# salidas_programables_easy_eda.net
KiCad netlist of a schematic drawn in EasyEDA
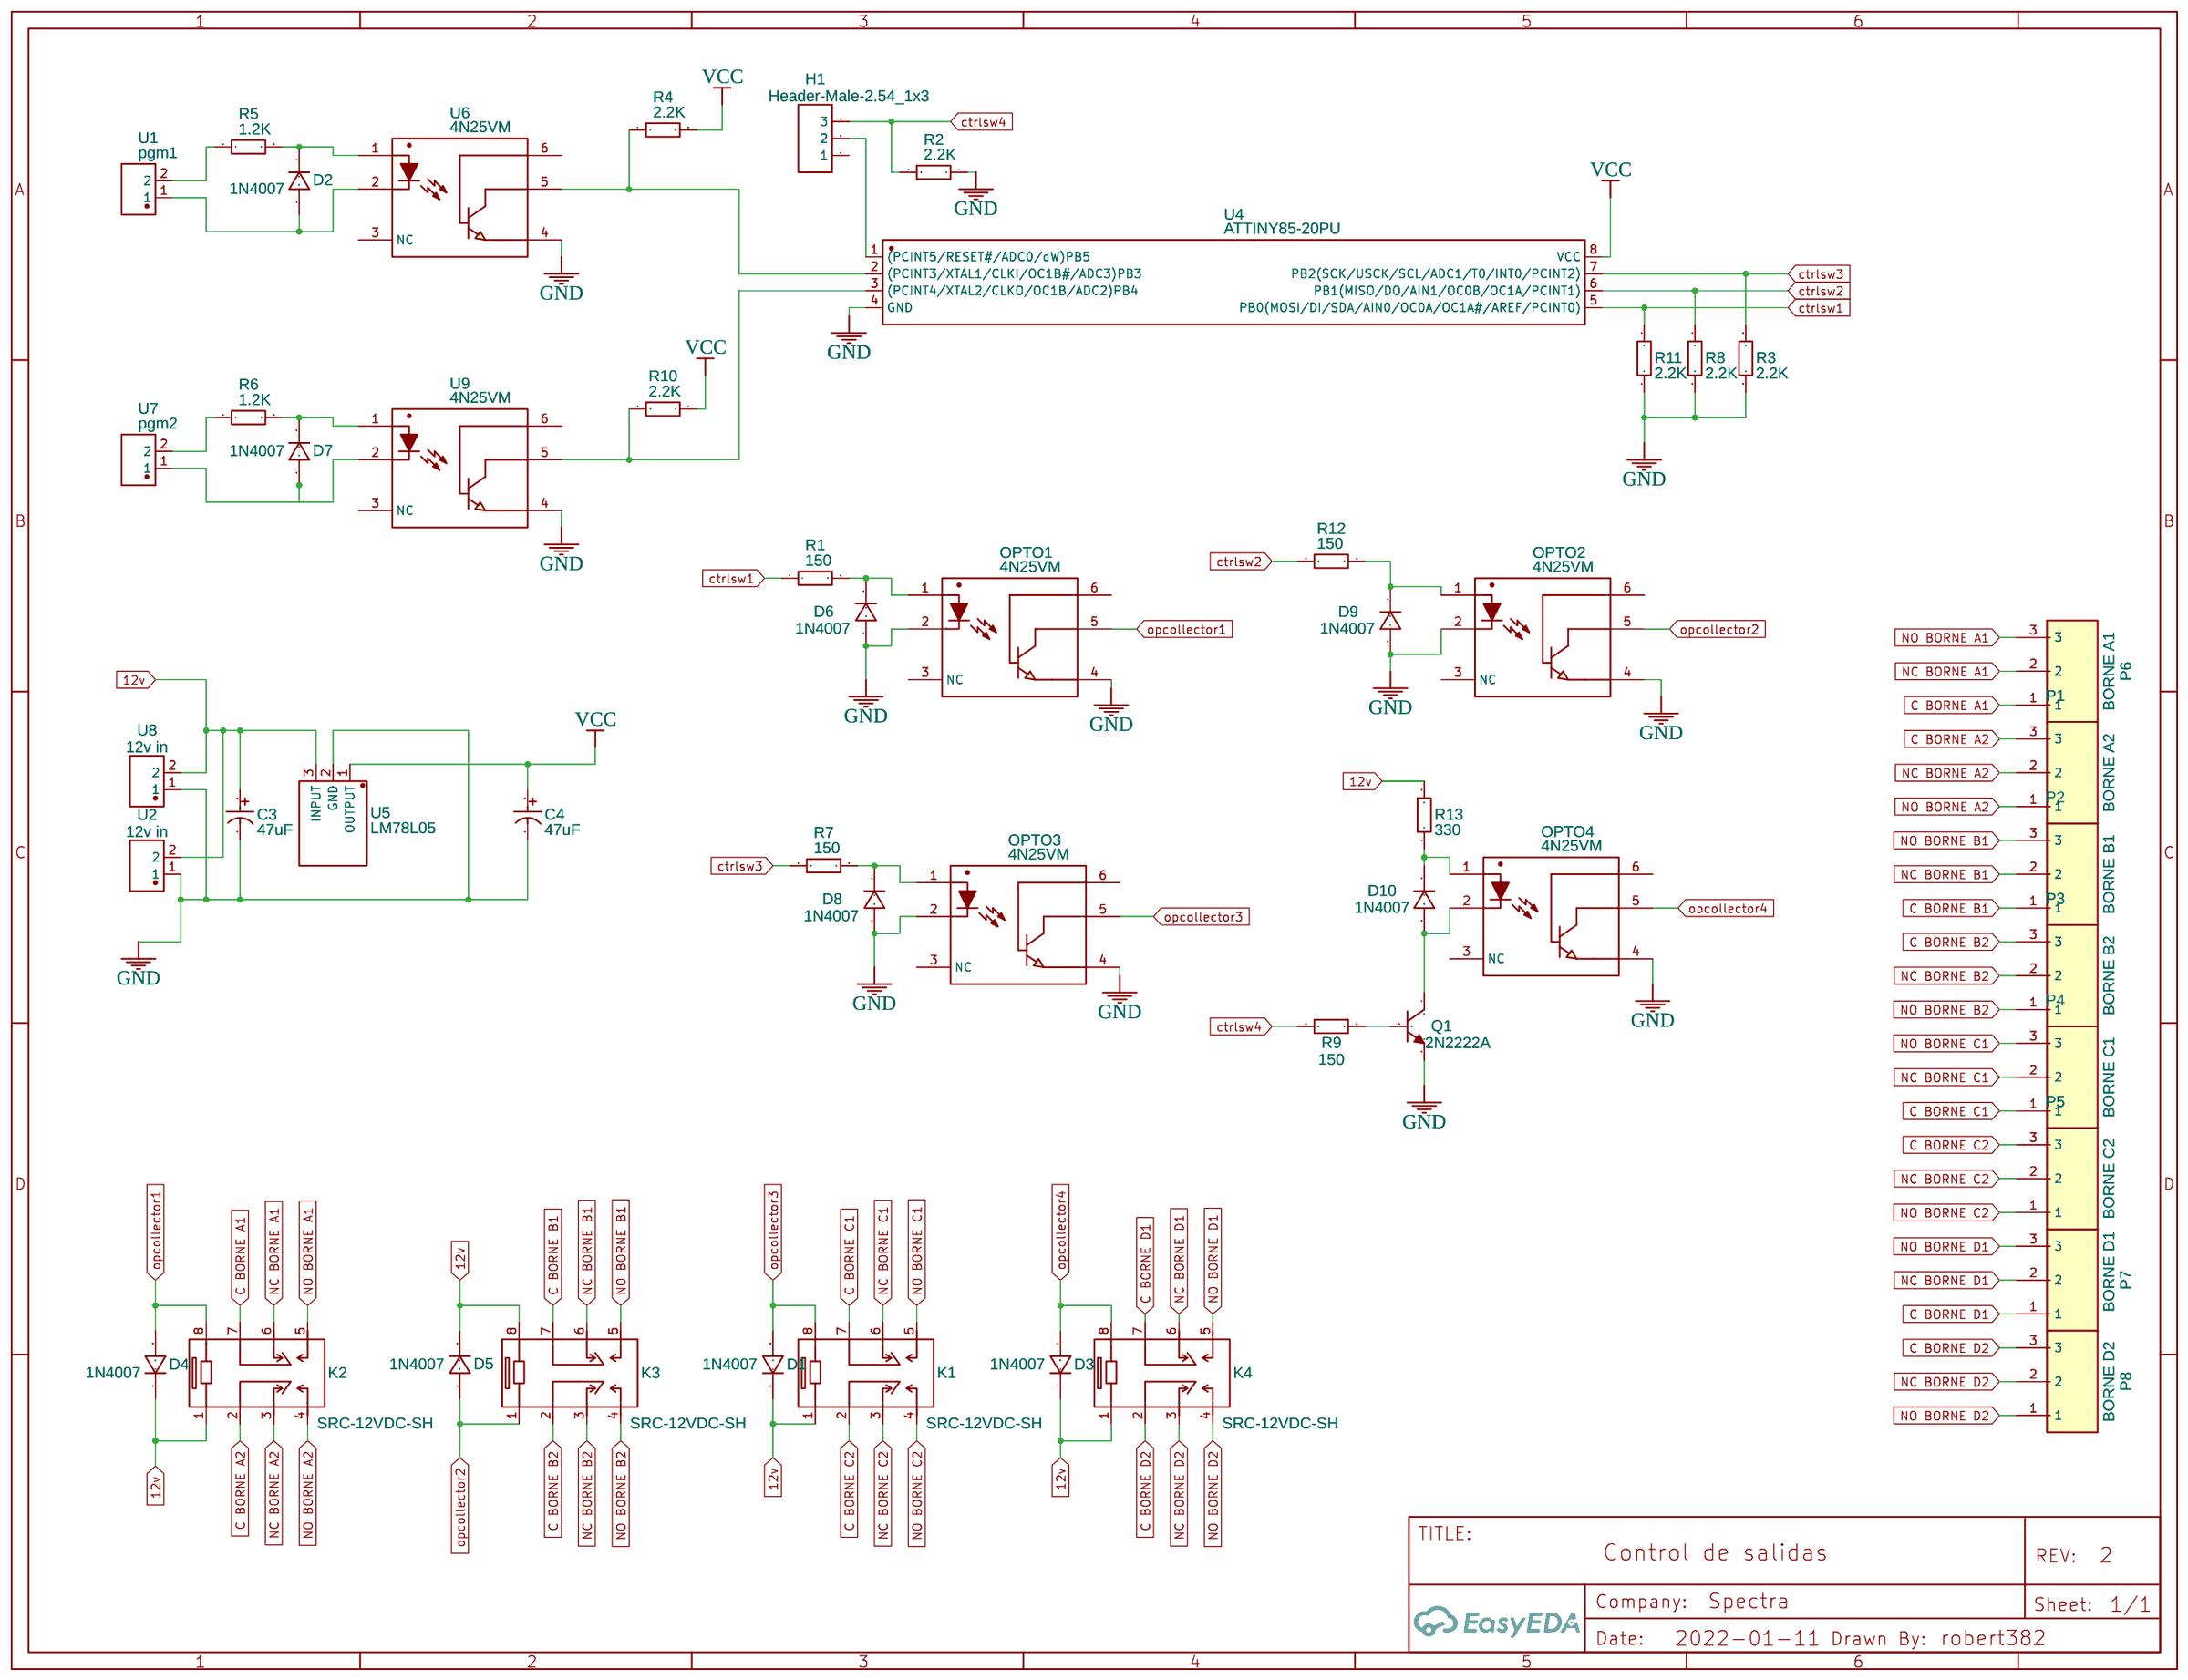
[diagram p0: schematic sheet]

(export (version "E")
  (design (tool "Eeschema 10.0.6"))
  (components
    (comp (ref "C3")
      (value "47uF")
      (fields
        (field (name "BOM_Manufacturer Part") "SH476M035F0800")
        (field (name "BOM_Supplier Part") "C99831")
      )
      (libsource (lib "") (part "SH476M035F0800"))
    )
    (comp (ref "C4")
      (value "47uF")
      (fields
        (field (name "BOM_Manufacturer Part") "SH476M035F0800")
        (field (name "BOM_Supplier Part") "C99831")
      )
      (libsource (lib "") (part "SH476M035F0800"))
    )
    (comp (ref "D1")
      (value "1N4007")
      (fields (field (name "BOM_Supplier Part") "C169152"))
      (libsource (lib "") (part "1N4007-C169152_1"))
    )
    (comp (ref "D2")
      (value "1N4007")
      (fields (field (name "BOM_Supplier Part") "C169152"))
      (libsource (lib "") (part "1N4007-C169152"))
    )
    (comp (ref "D3")
      (value "1N4007")
      (fields (field (name "BOM_Supplier Part") "C169152"))
      (libsource (lib "") (part "1N4007-C169152_1"))
    )
    (comp (ref "D4")
      (value "1N4007")
      (fields (field (name "BOM_Supplier Part") "C169152"))
      (libsource (lib "") (part "1N4007-C169152_1"))
    )
    (comp (ref "D5")
      (value "1N4007")
      (fields (field (name "BOM_Supplier Part") "C169152"))
      (libsource (lib "") (part "1N4007-C169152"))
    )
    (comp (ref "D6")
      (value "1N4007")
      (fields (field (name "BOM_Supplier Part") "C169152"))
      (libsource (lib "") (part "1N4007-C169152"))
    )
    (comp (ref "D7")
      (value "1N4007")
      (fields (field (name "BOM_Supplier Part") "C169152"))
      (libsource (lib "") (part "1N4007-C169152"))
    )
    (comp (ref "D8")
      (value "1N4007")
      (fields (field (name "BOM_Supplier Part") "C169152"))
      (libsource (lib "") (part "1N4007-C169152"))
    )
    (comp (ref "D9")
      (value "1N4007")
      (fields (field (name "BOM_Supplier Part") "C169152"))
      (libsource (lib "") (part "1N4007-C169152"))
    )
    (comp (ref "D10")
      (value "1N4007")
      (fields (field (name "BOM_Supplier Part") "C169152"))
      (libsource (lib "") (part "1N4007-C169152"))
    )
    (comp (ref "H1")
      (value "Header-Male-2.54_1x3")
      (fields
        (field (name "BOM_Manufacturer Part") "Header2.54mm 1*3P")
        (field (name "BOM_Supplier Part") "C49257")
      )
      (libsource (lib "") (part "Header-Male-2.54_1x3"))
    )
    (comp (ref "K1")
      (value "SRC-12VDC-SH")
      (fields (field (name "BOM_Supplier Part") "C192464"))
      (libsource (lib "") (part "SRC-12VDC-SH"))
    )
    (comp (ref "K2")
      (value "SRC-12VDC-SH")
      (fields (field (name "BOM_Supplier Part") "C192464"))
      (libsource (lib "") (part "SRC-12VDC-SH"))
    )
    (comp (ref "K3")
      (value "SRC-12VDC-SH")
      (fields (field (name "BOM_Supplier Part") "C192464"))
      (libsource (lib "") (part "SRC-12VDC-SH"))
    )
    (comp (ref "K4")
      (value "SRC-12VDC-SH")
      (fields (field (name "BOM_Supplier Part") "C192464"))
      (libsource (lib "") (part "SRC-12VDC-SH"))
    )
    (comp (ref "OPTO1")
      (value "4N25VM")
      (fields (field (name "BOM_Supplier Part") "C898943"))
      (libsource (lib "") (part "4N25VM"))
    )
    (comp (ref "OPTO2")
      (value "4N25VM")
      (fields (field (name "BOM_Supplier Part") "C898943"))
      (libsource (lib "") (part "4N25VM"))
    )
    (comp (ref "OPTO3")
      (value "4N25VM")
      (fields (field (name "BOM_Supplier Part") "C898943"))
      (libsource (lib "") (part "4N25VM"))
    )
    (comp (ref "OPTO4")
      (value "4N25VM")
      (fields (field (name "BOM_Supplier Part") "C898943"))
      (libsource (lib "") (part "4N25VM"))
    )
    (comp (ref "P1")
      (value "BORNE A2")
      (fields
        (field (name "BOM_Manufacturer Part") "WJ126V-5.0-3P")
        (field (name "BOM_Supplier Part") "C8401")
      )
      (libsource (lib "") (part "WJ126V-5.0-3P"))
    )
    (comp (ref "P2")
      (value "BORNE B1")
      (fields
        (field (name "BOM_Manufacturer Part") "WJ126V-5.0-3P")
        (field (name "BOM_Supplier Part") "C8401")
      )
      (libsource (lib "") (part "WJ126V-5.0-3P"))
    )
    (comp (ref "P3")
      (value "BORNE B2")
      (fields
        (field (name "BOM_Manufacturer Part") "WJ126V-5.0-3P")
        (field (name "BOM_Supplier Part") "C8401")
      )
      (libsource (lib "") (part "WJ126V-5.0-3P"))
    )
    (comp (ref "P4")
      (value "BORNE C1")
      (fields
        (field (name "BOM_Manufacturer Part") "WJ126V-5.0-3P")
        (field (name "BOM_Supplier Part") "C8401")
      )
      (libsource (lib "") (part "WJ126V-5.0-3P"))
    )
    (comp (ref "P5")
      (value "BORNE C2")
      (fields
        (field (name "BOM_Manufacturer Part") "WJ126V-5.0-3P")
        (field (name "BOM_Supplier Part") "C8401")
      )
      (libsource (lib "") (part "WJ126V-5.0-3P"))
    )
    (comp (ref "P6")
      (value "BORNE A1")
      (fields
        (field (name "BOM_Manufacturer Part") "WJ126V-5.0-3P")
        (field (name "BOM_Supplier Part") "C8401")
      )
      (libsource (lib "") (part "WJ126V-5.0-3P"))
    )
    (comp (ref "P7")
      (value "BORNE D1")
      (fields
        (field (name "BOM_Manufacturer Part") "WJ126V-5.0-3P")
        (field (name "BOM_Supplier Part") "C8401")
      )
      (libsource (lib "") (part "WJ126V-5.0-3P"))
    )
    (comp (ref "P8")
      (value "BORNE D2")
      (fields
        (field (name "BOM_Manufacturer Part") "WJ126V-5.0-3P")
        (field (name "BOM_Supplier Part") "C8401")
      )
      (libsource (lib "") (part "WJ126V-5.0-3P"))
    )
    (comp (ref "Q1")
      (value "2N2222A")
      (fields (field (name "BOM_Supplier Part") "C358533"))
      (libsource (lib "") (part "2N2222A"))
    )
    (comp (ref "R1")
      (value "150")
      (fields (field (name "BOM_Supplier Part") "C119160"))
      (libsource (lib "") (part "MF1/8W-150Ω±1% T52"))
    )
    (comp (ref "R2")
      (value "2.2K")
      (fields (field (name "BOM_Supplier Part") "C119331"))
      (libsource (lib "") (part "MF1/4W-2.2KΩ±1% T52_1"))
    )
    (comp (ref "R3")
      (value "2.2K")
      (fields (field (name "BOM_Supplier Part") "C119331"))
      (libsource (lib "") (part "MF1/4W-2.2KΩ±1% T52_2"))
    )
    (comp (ref "R4")
      (value "2.2K")
      (fields (field (name "BOM_Supplier Part") "C119331"))
      (libsource (lib "") (part "MF1/4W-2.2KΩ±1% T52"))
    )
    (comp (ref "R5")
      (value "1.2K")
      (fields (field (name "BOM_Supplier Part") "C119872"))
      (libsource (lib "") (part "CF1/6W-1.2KΩ±5% T52"))
    )
    (comp (ref "R6")
      (value "1.2K")
      (fields (field (name "BOM_Supplier Part") "C119872"))
      (libsource (lib "") (part "CF1/6W-1.2KΩ±5% T52"))
    )
    (comp (ref "R7")
      (value "150")
      (fields (field (name "BOM_Supplier Part") "C119160"))
      (libsource (lib "") (part "MF1/8W-150Ω±1% T52"))
    )
    (comp (ref "R8")
      (value "2.2K")
      (fields (field (name "BOM_Supplier Part") "C119331"))
      (libsource (lib "") (part "MF1/4W-2.2KΩ±1% T52_2"))
    )
    (comp (ref "R9")
      (value "150")
      (fields (field (name "BOM_Supplier Part") "C119160"))
      (libsource (lib "") (part "MF1/8W-150Ω±1% T52"))
    )
    (comp (ref "R10")
      (value "2.2K")
      (fields (field (name "BOM_Supplier Part") "C119331"))
      (libsource (lib "") (part "MF1/4W-2.2KΩ±1% T52_1"))
    )
    (comp (ref "R11")
      (value "2.2K")
      (fields (field (name "BOM_Supplier Part") "C119331"))
      (libsource (lib "") (part "MF1/4W-2.2KΩ±1% T52_2"))
    )
    (comp (ref "R12")
      (value "150")
      (fields (field (name "BOM_Supplier Part") "C119160"))
      (libsource (lib "") (part "MF1/8W-150Ω±1% T52"))
    )
    (comp (ref "R13")
      (value "330")
      (fields (field (name "BOM_Supplier Part") "C10322"))
      (libsource (lib "") (part "330Ω (331) ±5%"))
    )
    (comp (ref "U1")
      (value "pgm1")
      (fields
        (field (name "BOM_Manufacturer Part") "KY0200500000G")
        (field (name "BOM_Supplier Part") "C967069")
      )
      (libsource (lib "") (part "KY0200500000G"))
    )
    (comp (ref "U2")
      (value "12v in")
      (fields
        (field (name "BOM_Manufacturer Part") "KY0200500000G")
        (field (name "BOM_Supplier Part") "C967069")
      )
      (libsource (lib "") (part "KY0200500000G"))
    )
    (comp (ref "U4")
      (value "ATTINY85-20PU")
      (fields (field (name "BOM_Supplier Part") "C965497"))
      (libsource (lib "") (part "ATTINY85-20PU"))
    )
    (comp (ref "U5")
      (value "LM78L05")
      (fields
        (field (name "BOM_Manufacturer Part") "LM78L05ACZXA")
        (field (name "BOM_Supplier Part") "C236945")
      )
      (libsource (lib "") (part "LM78L05ACZXA"))
    )
    (comp (ref "U6")
      (value "4N25VM")
      (fields (field (name "BOM_Supplier Part") "C898943"))
      (libsource (lib "") (part "4N25VM_1"))
    )
    (comp (ref "U7")
      (value "pgm2")
      (fields
        (field (name "BOM_Manufacturer Part") "KY0200500000G")
        (field (name "BOM_Supplier Part") "C967069")
      )
      (libsource (lib "") (part "KY0200500000G"))
    )
    (comp (ref "U8")
      (value "12v in")
      (fields
        (field (name "BOM_Manufacturer Part") "KY0200500000G")
        (field (name "BOM_Supplier Part") "C967069")
      )
      (libsource (lib "") (part "KY0200500000G"))
    )
    (comp (ref "U9")
      (value "4N25VM")
      (fields (field (name "BOM_Supplier Part") "C898943"))
      (libsource (lib "") (part "4N25VM_1"))
    )
  )
  (nets
    (net (code "1") (name "12v") (class "Default")
      (node (ref "C3") (pin "1") (pinfunction "1_1") (pintype "input"))
      (node (ref "D1") (pin "1") (pinfunction "1_1") (pintype "unspecified"))
      (node (ref "D3") (pin "1") (pinfunction "1_1") (pintype "unspecified"))
      (node (ref "D4") (pin "1") (pinfunction "1_1") (pintype "unspecified"))
      (node (ref "D5") (pin "1") (pinfunction "1_1") (pintype "unspecified"))
      (node (ref "K1") (pin "1") (pinfunction "1_1") (pintype "unspecified"))
      (node (ref "K2") (pin "1") (pinfunction "1_1") (pintype "unspecified"))
      (node (ref "K3") (pin "8") (pinfunction "8_8") (pintype "unspecified"))
      (node (ref "K4") (pin "1") (pinfunction "1_1") (pintype "unspecified"))
      (node (ref "R13") (pin "2") (pinfunction "2_2") (pintype "unspecified"))
      (node (ref "U2") (pin "2") (pinfunction "2_2") (pintype "unspecified"))
      (node (ref "U5") (pin "3") (pinfunction "INPUT_3") (pintype "unspecified"))
      (node (ref "U8") (pin "2") (pinfunction "2_2") (pintype "unspecified"))
    )
    (net (code "2") (name "C BORNE A1") (class "Default")
      (node (ref "K2") (pin "7") (pinfunction "7_7") (pintype "unspecified"))
      (node (ref "P6") (pin "1") (pinfunction "1_1") (pintype "input"))
    )
    (net (code "3") (name "C BORNE A2") (class "Default")
      (node (ref "K2") (pin "2") (pinfunction "2_2") (pintype "unspecified"))
      (node (ref "P1") (pin "3") (pinfunction "3_3") (pintype "input"))
    )
    (net (code "4") (name "C BORNE B1") (class "Default")
      (node (ref "K3") (pin "7") (pinfunction "7_7") (pintype "unspecified"))
      (node (ref "P2") (pin "1") (pinfunction "1_1") (pintype "input"))
    )
    (net (code "5") (name "C BORNE B2") (class "Default")
      (node (ref "K3") (pin "2") (pinfunction "2_2") (pintype "unspecified"))
      (node (ref "P3") (pin "3") (pinfunction "3_3") (pintype "input"))
    )
    (net (code "6") (name "C BORNE C1") (class "Default")
      (node (ref "K1") (pin "7") (pinfunction "7_7") (pintype "unspecified"))
      (node (ref "P4") (pin "1") (pinfunction "1_1") (pintype "input"))
    )
    (net (code "7") (name "C BORNE C2") (class "Default")
      (node (ref "K1") (pin "2") (pinfunction "2_2") (pintype "unspecified"))
      (node (ref "P5") (pin "3") (pinfunction "3_3") (pintype "input"))
    )
    (net (code "8") (name "C BORNE D1") (class "Default")
      (node (ref "K4") (pin "7") (pinfunction "7_7") (pintype "unspecified"))
      (node (ref "P7") (pin "1") (pinfunction "1_1") (pintype "input"))
    )
    (net (code "9") (name "C BORNE D2") (class "Default")
      (node (ref "K4") (pin "2") (pinfunction "2_2") (pintype "unspecified"))
      (node (ref "P8") (pin "3") (pinfunction "3_3") (pintype "input"))
    )
    (net (code "10") (name "GND") (class "Default")
      (node (ref "C3") (pin "2") (pinfunction "2_2") (pintype "input"))
      (node (ref "C4") (pin "2") (pinfunction "2_2") (pintype "input"))
      (node (ref "D6") (pin "2") (pinfunction "2_2") (pintype "unspecified"))
      (node (ref "D8") (pin "2") (pinfunction "2_2") (pintype "unspecified"))
      (node (ref "D9") (pin "2") (pinfunction "2_2") (pintype "unspecified"))
      (node (ref "OPTO1") (pin "2") (pinfunction "C_2") (pintype "unspecified"))
      (node (ref "OPTO1") (pin "4") (pinfunction "E_4") (pintype "unspecified"))
      (node (ref "OPTO2") (pin "2") (pinfunction "C_2") (pintype "unspecified"))
      (node (ref "OPTO2") (pin "4") (pinfunction "E_4") (pintype "unspecified"))
      (node (ref "OPTO3") (pin "2") (pinfunction "C_2") (pintype "unspecified"))
      (node (ref "OPTO3") (pin "4") (pinfunction "E_4") (pintype "unspecified"))
      (node (ref "OPTO4") (pin "4") (pinfunction "E_4") (pintype "unspecified"))
      (node (ref "Q1") (pin "3") (pinfunction "E_3") (pintype "unspecified"))
      (node (ref "R11") (pin "1") (pinfunction "1_1") (pintype "unspecified"))
      (node (ref "R2") (pin "1") (pinfunction "1_1") (pintype "unspecified"))
      (node (ref "R3") (pin "1") (pinfunction "1_1") (pintype "unspecified"))
      (node (ref "R8") (pin "1") (pinfunction "1_1") (pintype "unspecified"))
      (node (ref "U2") (pin "1") (pinfunction "1_1") (pintype "unspecified"))
      (node (ref "U4") (pin "4") (pinfunction "GND_4") (pintype "unspecified"))
      (node (ref "U5") (pin "2") (pinfunction "GND_2") (pintype "unspecified"))
      (node (ref "U6") (pin "4") (pinfunction "E_4") (pintype "unspecified"))
      (node (ref "U8") (pin "1") (pinfunction "1_1") (pintype "unspecified"))
      (node (ref "U9") (pin "4") (pinfunction "E_4") (pintype "unspecified"))
    )
    (net (code "11") (name "NC BORNE A1") (class "Default")
      (node (ref "K2") (pin "6") (pinfunction "6_6") (pintype "unspecified"))
      (node (ref "P6") (pin "2") (pinfunction "2_2") (pintype "input"))
    )
    (net (code "12") (name "NC BORNE A2") (class "Default")
      (node (ref "K2") (pin "3") (pinfunction "3_3") (pintype "unspecified"))
      (node (ref "P1") (pin "2") (pinfunction "2_2") (pintype "input"))
    )
    (net (code "13") (name "NC BORNE B1") (class "Default")
      (node (ref "K3") (pin "6") (pinfunction "6_6") (pintype "unspecified"))
      (node (ref "P2") (pin "2") (pinfunction "2_2") (pintype "input"))
    )
    (net (code "14") (name "NC BORNE B2") (class "Default")
      (node (ref "K3") (pin "3") (pinfunction "3_3") (pintype "unspecified"))
      (node (ref "P3") (pin "2") (pinfunction "2_2") (pintype "input"))
    )
    (net (code "15") (name "NC BORNE C1") (class "Default")
      (node (ref "K1") (pin "6") (pinfunction "6_6") (pintype "unspecified"))
      (node (ref "P4") (pin "2") (pinfunction "2_2") (pintype "input"))
    )
    (net (code "16") (name "NC BORNE C2") (class "Default")
      (node (ref "K1") (pin "3") (pinfunction "3_3") (pintype "unspecified"))
      (node (ref "P5") (pin "2") (pinfunction "2_2") (pintype "input"))
    )
    (net (code "17") (name "NC BORNE D1") (class "Default")
      (node (ref "K4") (pin "6") (pinfunction "6_6") (pintype "unspecified"))
      (node (ref "P7") (pin "2") (pinfunction "2_2") (pintype "input"))
    )
    (net (code "18") (name "NC BORNE D2") (class "Default")
      (node (ref "K4") (pin "3") (pinfunction "3_3") (pintype "unspecified"))
      (node (ref "P8") (pin "2") (pinfunction "2_2") (pintype "input"))
    )
    (net (code "19") (name "NO BORNE A1") (class "Default")
      (node (ref "K2") (pin "5") (pinfunction "5_5") (pintype "unspecified"))
      (node (ref "P6") (pin "3") (pinfunction "3_3") (pintype "input"))
    )
    (net (code "20") (name "NO BORNE A2") (class "Default")
      (node (ref "K2") (pin "4") (pinfunction "4_4") (pintype "unspecified"))
      (node (ref "P1") (pin "1") (pinfunction "1_1") (pintype "input"))
    )
    (net (code "21") (name "NO BORNE B1") (class "Default")
      (node (ref "K3") (pin "5") (pinfunction "5_5") (pintype "unspecified"))
      (node (ref "P2") (pin "3") (pinfunction "3_3") (pintype "input"))
    )
    (net (code "22") (name "NO BORNE B2") (class "Default")
      (node (ref "K3") (pin "4") (pinfunction "4_4") (pintype "unspecified"))
      (node (ref "P3") (pin "1") (pinfunction "1_1") (pintype "input"))
    )
    (net (code "23") (name "NO BORNE C1") (class "Default")
      (node (ref "K1") (pin "5") (pinfunction "5_5") (pintype "unspecified"))
      (node (ref "P4") (pin "3") (pinfunction "3_3") (pintype "input"))
    )
    (net (code "24") (name "NO BORNE C2") (class "Default")
      (node (ref "K1") (pin "4") (pinfunction "4_4") (pintype "unspecified"))
      (node (ref "P5") (pin "1") (pinfunction "1_1") (pintype "input"))
    )
    (net (code "25") (name "NO BORNE D1") (class "Default")
      (node (ref "K4") (pin "5") (pinfunction "5_5") (pintype "unspecified"))
      (node (ref "P7") (pin "3") (pinfunction "3_3") (pintype "input"))
    )
    (net (code "26") (name "NO BORNE D2") (class "Default")
      (node (ref "K4") (pin "4") (pinfunction "4_4") (pintype "unspecified"))
      (node (ref "P8") (pin "1") (pinfunction "1_1") (pintype "input"))
    )
    (net (code "27") (name "Net-(D2-Pad2)") (class "Default")
      (node (ref "D2") (pin "2") (pinfunction "2_2") (pintype "unspecified"))
      (node (ref "U1") (pin "1") (pinfunction "1_1") (pintype "unspecified"))
      (node (ref "U6") (pin "2") (pinfunction "C_2") (pintype "unspecified"))
    )
    (net (code "28") (name "Net-(D7-Pad2)") (class "Default")
      (node (ref "D7") (pin "2") (pinfunction "2_2") (pintype "unspecified"))
      (node (ref "U7") (pin "1") (pinfunction "1_1") (pintype "unspecified"))
      (node (ref "U9") (pin "2") (pinfunction "C_2") (pintype "unspecified"))
    )
    (net (code "29") (name "Net-(OPTO1-A)") (class "Default")
      (node (ref "D6") (pin "1") (pinfunction "1_1") (pintype "unspecified"))
      (node (ref "OPTO1") (pin "1") (pinfunction "A_1") (pintype "unspecified"))
      (node (ref "R1") (pin "2") (pinfunction "2_2") (pintype "unspecified"))
    )
    (net (code "30") (name "Net-(OPTO2-A)") (class "Default")
      (node (ref "D9") (pin "1") (pinfunction "1_1") (pintype "unspecified"))
      (node (ref "OPTO2") (pin "1") (pinfunction "A_1") (pintype "unspecified"))
      (node (ref "R12") (pin "2") (pinfunction "2_2") (pintype "unspecified"))
    )
    (net (code "31") (name "Net-(OPTO3-A)") (class "Default")
      (node (ref "D8") (pin "1") (pinfunction "1_1") (pintype "unspecified"))
      (node (ref "OPTO3") (pin "1") (pinfunction "A_1") (pintype "unspecified"))
      (node (ref "R7") (pin "2") (pinfunction "2_2") (pintype "unspecified"))
    )
    (net (code "32") (name "Net-(OPTO4-A)") (class "Default")
      (node (ref "D10") (pin "1") (pinfunction "1_1") (pintype "unspecified"))
      (node (ref "OPTO4") (pin "1") (pinfunction "A_1") (pintype "unspecified"))
      (node (ref "R13") (pin "1") (pinfunction "1_1") (pintype "unspecified"))
    )
    (net (code "33") (name "Net-(Q1-B)") (class "Default")
      (node (ref "Q1") (pin "2") (pinfunction "B_2") (pintype "unspecified"))
      (node (ref "R9") (pin "2") (pinfunction "2_2") (pintype "unspecified"))
    )
    (net (code "34") (name "Net-(Q1-C)") (class "Default")
      (node (ref "D10") (pin "2") (pinfunction "2_2") (pintype "unspecified"))
      (node (ref "OPTO4") (pin "2") (pinfunction "C_2") (pintype "unspecified"))
      (node (ref "Q1") (pin "1") (pinfunction "C_1") (pintype "unspecified"))
    )
    (net (code "35") (name "Net-(R5-Pad1)") (class "Default")
      (node (ref "R5") (pin "1") (pinfunction "1_1") (pintype "unspecified"))
      (node (ref "U1") (pin "2") (pinfunction "2_2") (pintype "unspecified"))
    )
    (net (code "36") (name "Net-(R6-Pad1)") (class "Default")
      (node (ref "R6") (pin "1") (pinfunction "1_1") (pintype "unspecified"))
      (node (ref "U7") (pin "2") (pinfunction "2_2") (pintype "unspecified"))
    )
    (net (code "37") (name "Net-(U4-(PCINT3{slash}XTAL1{slash}CLKI{slash}OC1B#{slash}ADC3)PB3)") (class "Default")
      (node (ref "R4") (pin "1") (pinfunction "1_1") (pintype "unspecified"))
      (node (ref "U4") (pin "2") (pinfunction "(PCINT3/XTAL1/CLKI/OC1B#/ADC3)PB3_2") (pintype "unspecified"))
      (node (ref "U6") (pin "5") (pinfunction "C_5") (pintype "unspecified"))
    )
    (net (code "38") (name "Net-(U4-(PCINT4{slash}XTAL2{slash}CLKO{slash}OC1B{slash}ADC2)PB4)") (class "Default")
      (node (ref "R10") (pin "2") (pinfunction "2_2") (pintype "unspecified"))
      (node (ref "U4") (pin "3") (pinfunction "(PCINT4/XTAL2/CLKO/OC1B/ADC2)PB4_3") (pintype "unspecified"))
      (node (ref "U9") (pin "5") (pinfunction "C_5") (pintype "unspecified"))
    )
    (net (code "39") (name "Net-(U4-(PCINT5{slash}RESET#{slash}ADC0{slash}dW)PB5)") (class "Default")
      (node (ref "H1") (pin "2") (pinfunction "2_2") (pintype "input"))
      (node (ref "U4") (pin "1") (pinfunction "(PCINT5/RESET#/ADC0/dW)PB5_1") (pintype "unspecified"))
    )
    (net (code "40") (name "Net-(U6-A)") (class "Default")
      (node (ref "D2") (pin "1") (pinfunction "1_1") (pintype "unspecified"))
      (node (ref "R5") (pin "2") (pinfunction "2_2") (pintype "unspecified"))
      (node (ref "U6") (pin "1") (pinfunction "A_1") (pintype "unspecified"))
    )
    (net (code "41") (name "Net-(U9-A)") (class "Default")
      (node (ref "D7") (pin "1") (pinfunction "1_1") (pintype "unspecified"))
      (node (ref "R6") (pin "2") (pinfunction "2_2") (pintype "unspecified"))
      (node (ref "U9") (pin "1") (pinfunction "A_1") (pintype "unspecified"))
    )
    (net (code "42") (name "VCC") (class "Default")
      (node (ref "C4") (pin "1") (pinfunction "1_1") (pintype "input"))
      (node (ref "R10") (pin "1") (pinfunction "1_1") (pintype "unspecified"))
      (node (ref "R4") (pin "2") (pinfunction "2_2") (pintype "unspecified"))
      (node (ref "U4") (pin "8") (pinfunction "VCC_8") (pintype "unspecified"))
      (node (ref "U5") (pin "1") (pinfunction "OUTPUT_1") (pintype "unspecified"))
    )
    (net (code "43") (name "ctrlsw1") (class "Default")
      (node (ref "R1") (pin "1") (pinfunction "1_1") (pintype "unspecified"))
      (node (ref "R11") (pin "2") (pinfunction "2_2") (pintype "unspecified"))
      (node (ref "U4") (pin "5") (pinfunction "PB0(MOSI/DI/SDA/AIN0/OC0A/OC1A#/AREF/PCINT0)_5") (pintype "unspecified"))
    )
    (net (code "44") (name "ctrlsw2") (class "Default")
      (node (ref "R12") (pin "1") (pinfunction "1_1") (pintype "unspecified"))
      (node (ref "R8") (pin "2") (pinfunction "2_2") (pintype "unspecified"))
      (node (ref "U4") (pin "6") (pinfunction "PB1(MISO/DO/AIN1/OC0B/OC1A/PCINT1)_6") (pintype "unspecified"))
    )
    (net (code "45") (name "ctrlsw3") (class "Default")
      (node (ref "R3") (pin "2") (pinfunction "2_2") (pintype "unspecified"))
      (node (ref "R7") (pin "1") (pinfunction "1_1") (pintype "unspecified"))
      (node (ref "U4") (pin "7") (pinfunction "PB2(SCK/USCK/SCL/ADC1/T0/INT0/PCINT2)_7") (pintype "unspecified"))
    )
    (net (code "46") (name "ctrlsw4") (class "Default")
      (node (ref "H1") (pin "3") (pinfunction "3_3") (pintype "input"))
      (node (ref "R2") (pin "2") (pinfunction "2_2") (pintype "unspecified"))
      (node (ref "R9") (pin "1") (pinfunction "1_1") (pintype "unspecified"))
    )
    (net (code "47") (name "opcollector1") (class "Default")
      (node (ref "D4") (pin "2") (pinfunction "2_2") (pintype "unspecified"))
      (node (ref "K2") (pin "8") (pinfunction "8_8") (pintype "unspecified"))
      (node (ref "OPTO1") (pin "5") (pinfunction "C_5") (pintype "unspecified"))
    )
    (net (code "48") (name "opcollector2") (class "Default")
      (node (ref "D5") (pin "2") (pinfunction "2_2") (pintype "unspecified"))
      (node (ref "K3") (pin "1") (pinfunction "1_1") (pintype "unspecified"))
      (node (ref "OPTO2") (pin "5") (pinfunction "C_5") (pintype "unspecified"))
    )
    (net (code "49") (name "opcollector3") (class "Default")
      (node (ref "D1") (pin "2") (pinfunction "2_2") (pintype "unspecified"))
      (node (ref "K1") (pin "8") (pinfunction "8_8") (pintype "unspecified"))
      (node (ref "OPTO3") (pin "5") (pinfunction "C_5") (pintype "unspecified"))
    )
    (net (code "50") (name "opcollector4") (class "Default")
      (node (ref "D3") (pin "2") (pinfunction "2_2") (pintype "unspecified"))
      (node (ref "K4") (pin "8") (pinfunction "8_8") (pintype "unspecified"))
      (node (ref "OPTO4") (pin "5") (pinfunction "C_5") (pintype "unspecified"))
    )
    (net (code "51") (name "unconnected-(H1-Pad1)") (class "Default")
      (node (ref "H1") (pin "1") (pinfunction "1_1") (pintype "input"))
    )
    (net (code "52") (name "unconnected-(OPTO1-B-Pad6)") (class "Default")
      (node (ref "OPTO1") (pin "6") (pinfunction "B_6") (pintype "unspecified"))
    )
    (net (code "53") (name "unconnected-(OPTO1-NC-Pad3)") (class "Default")
      (node (ref "OPTO1") (pin "3") (pinfunction "NC_3") (pintype "unspecified"))
    )
    (net (code "54") (name "unconnected-(OPTO2-B-Pad6)") (class "Default")
      (node (ref "OPTO2") (pin "6") (pinfunction "B_6") (pintype "unspecified"))
    )
    (net (code "55") (name "unconnected-(OPTO2-NC-Pad3)") (class "Default")
      (node (ref "OPTO2") (pin "3") (pinfunction "NC_3") (pintype "unspecified"))
    )
    (net (code "56") (name "unconnected-(OPTO3-B-Pad6)") (class "Default")
      (node (ref "OPTO3") (pin "6") (pinfunction "B_6") (pintype "unspecified"))
    )
    (net (code "57") (name "unconnected-(OPTO3-NC-Pad3)") (class "Default")
      (node (ref "OPTO3") (pin "3") (pinfunction "NC_3") (pintype "unspecified"))
    )
    (net (code "58") (name "unconnected-(OPTO4-B-Pad6)") (class "Default")
      (node (ref "OPTO4") (pin "6") (pinfunction "B_6") (pintype "unspecified"))
    )
    (net (code "59") (name "unconnected-(OPTO4-NC-Pad3)") (class "Default")
      (node (ref "OPTO4") (pin "3") (pinfunction "NC_3") (pintype "unspecified"))
    )
    (net (code "60") (name "unconnected-(U6-B-Pad6)") (class "Default")
      (node (ref "U6") (pin "6") (pinfunction "B_6") (pintype "unspecified"))
    )
    (net (code "61") (name "unconnected-(U6-NC-Pad3)") (class "Default")
      (node (ref "U6") (pin "3") (pinfunction "NC_3") (pintype "unspecified"))
    )
    (net (code "62") (name "unconnected-(U9-B-Pad6)") (class "Default")
      (node (ref "U9") (pin "6") (pinfunction "B_6") (pintype "unspecified"))
    )
    (net (code "63") (name "unconnected-(U9-NC-Pad3)") (class "Default")
      (node (ref "U9") (pin "3") (pinfunction "NC_3") (pintype "unspecified"))
    )
  )
)
